# Source_Trans.net
KiCad netlist of a schematic drawn in Altium Designer
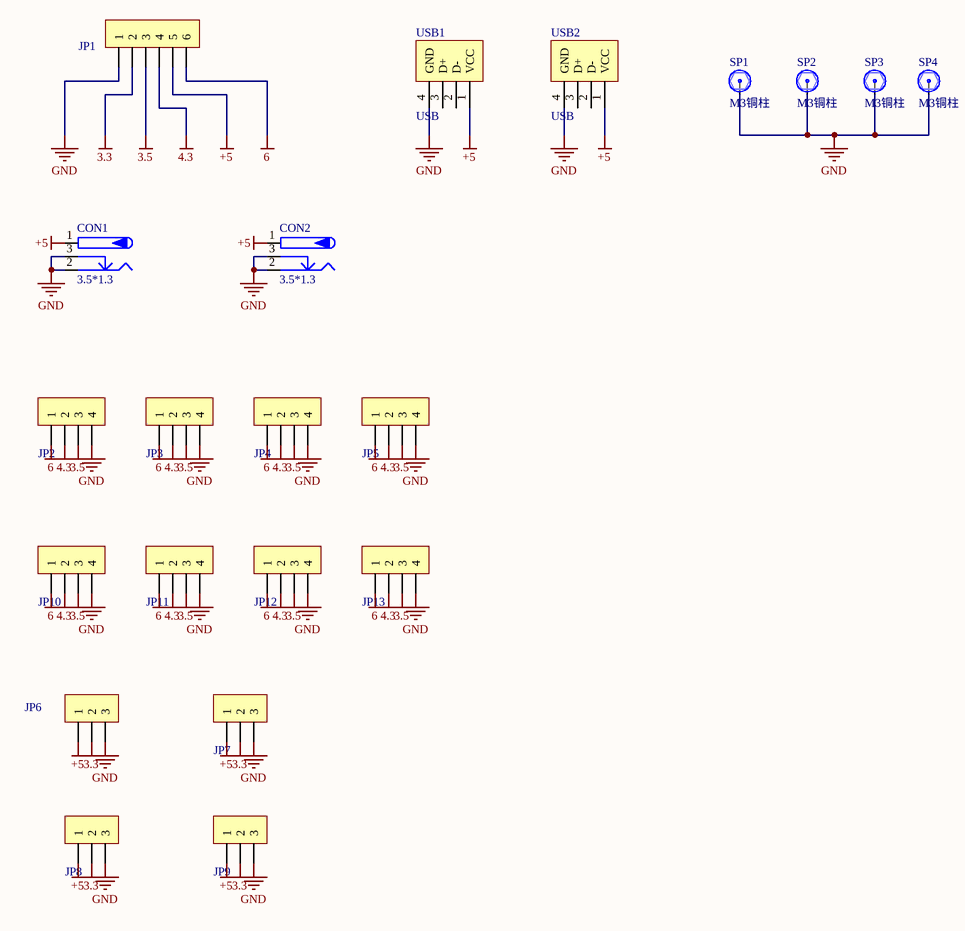
[diagram p0: Source_Trans.SchDoc]

(export (version "E")
  (design (tool "Eeschema 10.0.6"))
  (components
    (comp (ref "CON1")
      (value "3.5*1.3")
      (footprint "DC-005")
      (description "低压电源接口")
      (libsource (lib "接口") (part "P-DC"))
    )
    (comp (ref "CON2")
      (value "3.5*1.3")
      (footprint "DC-005")
      (description "低压电源接口")
      (libsource (lib "接口") (part "P-DC"))
    )
    (comp (ref "JP1")
      (value "HDR-1X6")
      (footprint "XH2.54-WS-6P")
      (description "6P接插件")
      (libsource (lib "XH2.54") (part "Header 6"))
    )
    (comp (ref "JP2")
      (value "HDR-1X4")
      (footprint "XH2.54-LI-4P")
      (description "4P接插件")
      (libsource (lib "XH2.54") (part "Header 4"))
    )
    (comp (ref "JP3")
      (value "HDR-1X4")
      (footprint "XH2.54-LI-4P")
      (description "4P接插件")
      (libsource (lib "XH2.54") (part "Header 4"))
    )
    (comp (ref "JP4")
      (value "HDR-1X4")
      (footprint "XH2.54-LI-4P")
      (description "4P接插件")
      (libsource (lib "XH2.54") (part "Header 4"))
    )
    (comp (ref "JP5")
      (value "HDR-1X4")
      (footprint "XH2.54-LI-4P")
      (description "4P接插件")
      (libsource (lib "XH2.54") (part "Header 4"))
    )
    (comp (ref "JP6")
      (value "HDR-1X3")
      (footprint "XH2.54-LI-3P")
      (description "3P接插件")
      (libsource (lib "XH2.54") (part "Header 3"))
    )
    (comp (ref "JP7")
      (value "HDR-1X3")
      (footprint "XH2.54-LI-3P")
      (description "3P接插件")
      (libsource (lib "XH2.54") (part "Header 3"))
    )
    (comp (ref "JP8")
      (value "HDR-1X3")
      (footprint "XH2.54-LI-3P")
      (description "3P接插件")
      (libsource (lib "XH2.54") (part "Header 3"))
    )
    (comp (ref "JP9")
      (value "HDR-1X3")
      (footprint "XH2.54-LI-3P")
      (description "3P接插件")
      (libsource (lib "XH2.54") (part "Header 3"))
    )
    (comp (ref "JP10")
      (value "HDR-1X4")
      (footprint "XH2.54-LI-4P")
      (description "4P接插件")
      (libsource (lib "XH2.54") (part "Header 4"))
    )
    (comp (ref "JP11")
      (value "HDR-1X4")
      (footprint "XH2.54-LI-4P")
      (description "4P接插件")
      (libsource (lib "XH2.54") (part "Header 4"))
    )
    (comp (ref "JP12")
      (value "HDR-1X4")
      (footprint "XH2.54-LI-4P")
      (description "4P接插件")
      (libsource (lib "XH2.54") (part "Header 4"))
    )
    (comp (ref "JP13")
      (value "HDR-1X4")
      (footprint "XH2.54-LI-4P")
      (description "4P接插件")
      (libsource (lib "XH2.54") (part "Header 4"))
    )
    (comp (ref "SP1")
      (value "M3铜柱")
      (footprint "M3x4_L")
      (description "铜柱")
      (libsource (lib "铜柱-测试点-电池座-蜂鸣器") (part "铜柱小焊盘"))
    )
    (comp (ref "SP2")
      (value "M3铜柱")
      (footprint "M3x4_L")
      (description "铜柱")
      (libsource (lib "铜柱-测试点-电池座-蜂鸣器") (part "铜柱小焊盘"))
    )
    (comp (ref "SP3")
      (value "M3铜柱")
      (footprint "M3x4_L")
      (description "铜柱")
      (libsource (lib "铜柱-测试点-电池座-蜂鸣器") (part "铜柱小焊盘"))
    )
    (comp (ref "SP4")
      (value "M3铜柱")
      (footprint "M3x4_L")
      (description "铜柱")
      (libsource (lib "铜柱-测试点-电池座-蜂鸣器") (part "铜柱小焊盘"))
    )
    (comp (ref "USB1")
      (value "USB")
      (footprint "USB-A/S_A")
      (description "USB-A型母接口")
      (libsource (lib "接口") (part "USB-A/S"))
    )
    (comp (ref "USB2")
      (value "USB")
      (footprint "USB-A/S_A")
      (description "USB-A型母接口")
      (libsource (lib "接口") (part "USB-A/S"))
    )
  )
  (nets
    (net (code "1") (name "+5") (class "Default")
      (node (ref "CON1") (pin "1") (pintype "power_in"))
      (node (ref "CON2") (pin "1") (pintype "power_in"))
      (node (ref "JP1") (pin "5") (pinfunction "5_5") (pintype "passive"))
      (node (ref "JP6") (pin "1") (pinfunction "1_1") (pintype "passive"))
      (node (ref "JP7") (pin "1") (pinfunction "1_1") (pintype "passive"))
      (node (ref "JP8") (pin "1") (pinfunction "1_1") (pintype "passive"))
      (node (ref "JP9") (pin "1") (pinfunction "1_1") (pintype "passive"))
      (node (ref "USB1") (pin "1") (pinfunction "VCC_1") (pintype "passive"))
      (node (ref "USB2") (pin "1") (pinfunction "VCC_1") (pintype "passive"))
    )
    (net (code "2") (name "3.3") (class "Default")
      (node (ref "JP1") (pin "2") (pinfunction "2_2") (pintype "passive"))
      (node (ref "JP6") (pin "2") (pinfunction "2_2") (pintype "passive"))
      (node (ref "JP7") (pin "2") (pinfunction "2_2") (pintype "passive"))
      (node (ref "JP8") (pin "2") (pinfunction "2_2") (pintype "passive"))
      (node (ref "JP9") (pin "2") (pinfunction "2_2") (pintype "passive"))
    )
    (net (code "3") (name "3.5") (class "Default")
      (node (ref "JP1") (pin "3") (pinfunction "3_3") (pintype "passive"))
      (node (ref "JP10") (pin "3") (pinfunction "3_3") (pintype "passive"))
      (node (ref "JP11") (pin "3") (pinfunction "3_3") (pintype "passive"))
      (node (ref "JP12") (pin "3") (pinfunction "3_3") (pintype "passive"))
      (node (ref "JP13") (pin "3") (pinfunction "3_3") (pintype "passive"))
      (node (ref "JP2") (pin "3") (pinfunction "3_3") (pintype "passive"))
      (node (ref "JP3") (pin "3") (pinfunction "3_3") (pintype "passive"))
      (node (ref "JP4") (pin "3") (pinfunction "3_3") (pintype "passive"))
      (node (ref "JP5") (pin "3") (pinfunction "3_3") (pintype "passive"))
    )
    (net (code "4") (name "4.3") (class "Default")
      (node (ref "JP1") (pin "4") (pinfunction "4_4") (pintype "passive"))
      (node (ref "JP10") (pin "2") (pinfunction "2_2") (pintype "passive"))
      (node (ref "JP11") (pin "2") (pinfunction "2_2") (pintype "passive"))
      (node (ref "JP12") (pin "2") (pinfunction "2_2") (pintype "passive"))
      (node (ref "JP13") (pin "2") (pinfunction "2_2") (pintype "passive"))
      (node (ref "JP2") (pin "2") (pinfunction "2_2") (pintype "passive"))
      (node (ref "JP3") (pin "2") (pinfunction "2_2") (pintype "passive"))
      (node (ref "JP4") (pin "2") (pinfunction "2_2") (pintype "passive"))
      (node (ref "JP5") (pin "2") (pinfunction "2_2") (pintype "passive"))
    )
    (net (code "5") (name "6") (class "Default")
      (node (ref "JP1") (pin "6") (pinfunction "6_6") (pintype "passive"))
      (node (ref "JP10") (pin "1") (pinfunction "1_1") (pintype "passive"))
      (node (ref "JP11") (pin "1") (pinfunction "1_1") (pintype "passive"))
      (node (ref "JP12") (pin "1") (pinfunction "1_1") (pintype "passive"))
      (node (ref "JP13") (pin "1") (pinfunction "1_1") (pintype "passive"))
      (node (ref "JP2") (pin "1") (pinfunction "1_1") (pintype "passive"))
      (node (ref "JP3") (pin "1") (pinfunction "1_1") (pintype "passive"))
      (node (ref "JP4") (pin "1") (pinfunction "1_1") (pintype "passive"))
      (node (ref "JP5") (pin "1") (pinfunction "1_1") (pintype "passive"))
    )
    (net (code "6") (name "GND") (class "Default")
      (node (ref "CON1") (pin "2") (pintype "power_in"))
      (node (ref "CON1") (pin "3") (pintype "power_in"))
      (node (ref "CON2") (pin "2") (pintype "power_in"))
      (node (ref "CON2") (pin "3") (pintype "power_in"))
      (node (ref "JP1") (pin "1") (pinfunction "1_1") (pintype "passive"))
      (node (ref "JP10") (pin "4") (pinfunction "4_4") (pintype "passive"))
      (node (ref "JP11") (pin "4") (pinfunction "4_4") (pintype "passive"))
      (node (ref "JP12") (pin "4") (pinfunction "4_4") (pintype "passive"))
      (node (ref "JP13") (pin "4") (pinfunction "4_4") (pintype "passive"))
      (node (ref "JP2") (pin "4") (pinfunction "4_4") (pintype "passive"))
      (node (ref "JP3") (pin "4") (pinfunction "4_4") (pintype "passive"))
      (node (ref "JP4") (pin "4") (pinfunction "4_4") (pintype "passive"))
      (node (ref "JP5") (pin "4") (pinfunction "4_4") (pintype "passive"))
      (node (ref "JP6") (pin "3") (pinfunction "3_3") (pintype "passive"))
      (node (ref "JP7") (pin "3") (pinfunction "3_3") (pintype "passive"))
      (node (ref "JP8") (pin "3") (pinfunction "3_3") (pintype "passive"))
      (node (ref "JP9") (pin "3") (pinfunction "3_3") (pintype "passive"))
      (node (ref "SP1") (pin "1") (pinfunction "1_1") (pintype "passive"))
      (node (ref "SP2") (pin "1") (pinfunction "1_1") (pintype "passive"))
      (node (ref "SP3") (pin "1") (pinfunction "1_1") (pintype "passive"))
      (node (ref "SP4") (pin "1") (pinfunction "1_1") (pintype "passive"))
      (node (ref "USB1") (pin "4") (pinfunction "GND_4") (pintype "passive"))
      (node (ref "USB2") (pin "4") (pinfunction "GND_4") (pintype "passive"))
    )
    (net (code "7") (name "unconnected-(USB1-D+-Pad3)") (class "Default")
      (node (ref "USB1") (pin "3") (pinfunction "D+_3") (pintype "passive"))
    )
    (net (code "8") (name "unconnected-(USB1-D--Pad2)") (class "Default")
      (node (ref "USB1") (pin "2") (pinfunction "D-_2") (pintype "passive"))
    )
    (net (code "9") (name "unconnected-(USB2-D+-Pad3)") (class "Default")
      (node (ref "USB2") (pin "3") (pinfunction "D+_3") (pintype "passive"))
    )
    (net (code "10") (name "unconnected-(USB2-D--Pad2)") (class "Default")
      (node (ref "USB2") (pin "2") (pinfunction "D-_2") (pintype "passive"))
    )
  )
)
